# speculator_minor_mainboard_76mm_v1.net
KiCad netlist of a schematic drawn in EAGLE
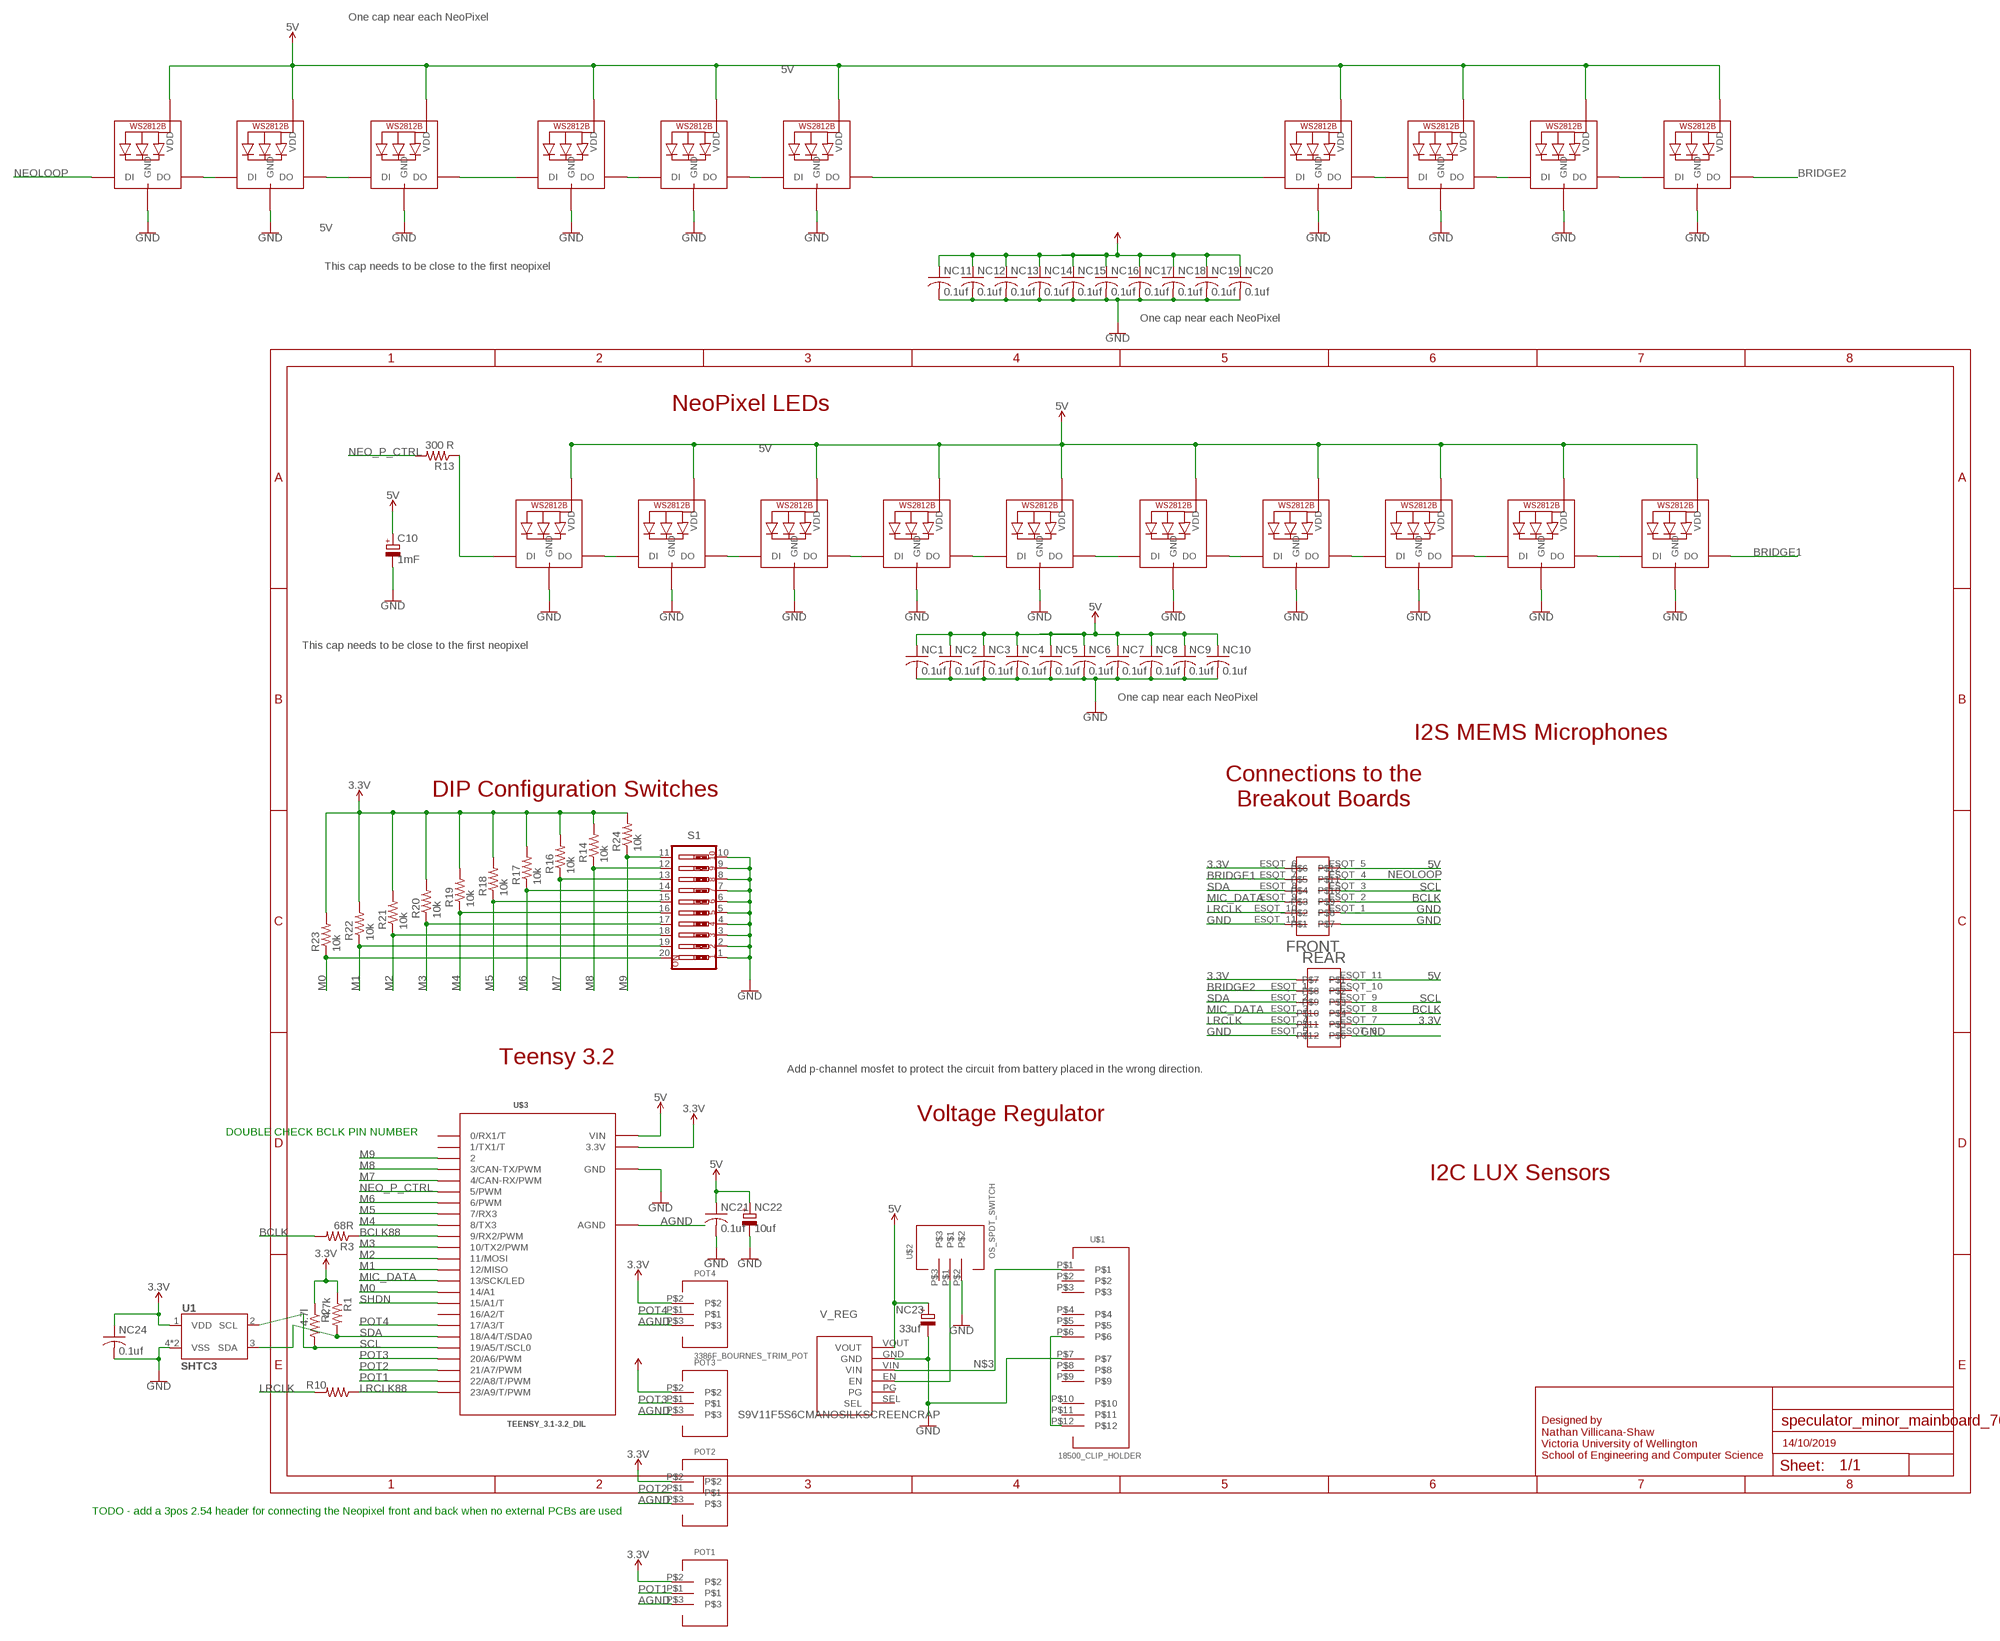
[diagram p0: schematic, sheet 1, part 1 of 2]
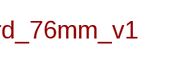
[diagram p1: schematic, sheet 1, part 2 of 2]

(export (version "E")
  (design (tool "Eeschema 10.0.6"))
  (components
    (comp (ref "C10")
      (value "1mF")
      (footprint "eagle-import:153CLV-1010")
      (libsource (lib "eagle-import") (part "CPOL-EU153CLV-1010"))
    )
    (comp (ref "FRONT")
      (value "SAMTEC_ESQT_2X6_THROUGH_HOLE")
      (footprint "eagle-import:SAMTEC_ESQT_2X6_THROUGH_HOLE")
      (libsource (lib "eagle-import") (part "SAMTEC_ESQT_2X6_THROUGH_HOLE"))
    )
    (comp (ref "NC1")
      (value "0.1uf")
      (footprint "eagle-import:C0805K")
      (libsource (lib "eagle-import") (part "C-USC0805K"))
    )
    (comp (ref "NC2")
      (value "0.1uf")
      (footprint "eagle-import:C0805K")
      (libsource (lib "eagle-import") (part "C-USC0805K"))
    )
    (comp (ref "NC3")
      (value "0.1uf")
      (footprint "eagle-import:C0805K")
      (libsource (lib "eagle-import") (part "C-USC0805K"))
    )
    (comp (ref "NC4")
      (value "0.1uf")
      (footprint "eagle-import:C0805K")
      (libsource (lib "eagle-import") (part "C-USC0805K"))
    )
    (comp (ref "NC5")
      (value "0.1uf")
      (footprint "eagle-import:C0805K")
      (libsource (lib "eagle-import") (part "C-USC0805K"))
    )
    (comp (ref "NC6")
      (value "0.1uf")
      (footprint "eagle-import:C0805K")
      (libsource (lib "eagle-import") (part "C-USC0805K"))
    )
    (comp (ref "NC7")
      (value "0.1uf")
      (footprint "eagle-import:C0805K")
      (libsource (lib "eagle-import") (part "C-USC0805K"))
    )
    (comp (ref "NC8")
      (value "0.1uf")
      (footprint "eagle-import:C0805K")
      (libsource (lib "eagle-import") (part "C-USC0805K"))
    )
    (comp (ref "NC9")
      (value "0.1uf")
      (footprint "eagle-import:C0805K")
      (libsource (lib "eagle-import") (part "C-USC0805K"))
    )
    (comp (ref "NC10")
      (value "0.1uf")
      (footprint "eagle-import:C0805K")
      (libsource (lib "eagle-import") (part "C-USC0805K"))
    )
    (comp (ref "NC11")
      (value "0.1uf")
      (footprint "eagle-import:C0805K")
      (libsource (lib "eagle-import") (part "C-USC0805K"))
    )
    (comp (ref "NC12")
      (value "0.1uf")
      (footprint "eagle-import:C0805K")
      (libsource (lib "eagle-import") (part "C-USC0805K"))
    )
    (comp (ref "NC13")
      (value "0.1uf")
      (footprint "eagle-import:C0805K")
      (libsource (lib "eagle-import") (part "C-USC0805K"))
    )
    (comp (ref "NC14")
      (value "0.1uf")
      (footprint "eagle-import:C0805K")
      (libsource (lib "eagle-import") (part "C-USC0805K"))
    )
    (comp (ref "NC15")
      (value "0.1uf")
      (footprint "eagle-import:C0805K")
      (libsource (lib "eagle-import") (part "C-USC0805K"))
    )
    (comp (ref "NC16")
      (value "0.1uf")
      (footprint "eagle-import:C0805K")
      (libsource (lib "eagle-import") (part "C-USC0805K"))
    )
    (comp (ref "NC17")
      (value "0.1uf")
      (footprint "eagle-import:C0805K")
      (libsource (lib "eagle-import") (part "C-USC0805K"))
    )
    (comp (ref "NC18")
      (value "0.1uf")
      (footprint "eagle-import:C0805K")
      (libsource (lib "eagle-import") (part "C-USC0805K"))
    )
    (comp (ref "NC19")
      (value "0.1uf")
      (footprint "eagle-import:C0805K")
      (libsource (lib "eagle-import") (part "C-USC0805K"))
    )
    (comp (ref "NC20")
      (value "0.1uf")
      (footprint "eagle-import:C0805K")
      (libsource (lib "eagle-import") (part "C-USC0805K"))
    )
    (comp (ref "NC21")
      (value "0.1uf")
      (footprint "eagle-import:C0805K")
      (libsource (lib "eagle-import") (part "C-USC0805K"))
    )
    (comp (ref "NC22")
      (value "10uf")
      (footprint "eagle-import:E2,5-7")
      (libsource (lib "eagle-import") (part "CPOL-EUE2.5-7"))
    )
    (comp (ref "NC23")
      (value "33uf")
      (footprint "eagle-import:E2,5-7")
      (libsource (lib "eagle-import") (part "CPOL-EUE2.5-7"))
    )
    (comp (ref "NC24")
      (value "0.1uf")
      (footprint "eagle-import:C0805K")
      (libsource (lib "eagle-import") (part "C-USC0805K"))
    )
    (comp (ref "NEO1")
      (value "WS2812B5050")
      (footprint "eagle-import:WS2812B")
      (libsource (lib "eagle-import") (part "WS2812B5050"))
    )
    (comp (ref "NEO2")
      (value "WS2812B5050")
      (footprint "eagle-import:WS2812B")
      (libsource (lib "eagle-import") (part "WS2812B5050"))
    )
    (comp (ref "NEO3")
      (value "WS2812B5050")
      (footprint "eagle-import:WS2812B")
      (libsource (lib "eagle-import") (part "WS2812B5050"))
    )
    (comp (ref "NEO4")
      (value "WS2812B5050")
      (footprint "eagle-import:WS2812B")
      (libsource (lib "eagle-import") (part "WS2812B5050"))
    )
    (comp (ref "NEO5")
      (value "WS2812B5050")
      (footprint "eagle-import:WS2812B")
      (libsource (lib "eagle-import") (part "WS2812B5050"))
    )
    (comp (ref "NEO6")
      (value "WS2812B5050")
      (footprint "eagle-import:WS2812B")
      (libsource (lib "eagle-import") (part "WS2812B5050"))
    )
    (comp (ref "NEO7")
      (value "WS2812B5050")
      (footprint "eagle-import:WS2812B")
      (libsource (lib "eagle-import") (part "WS2812B5050"))
    )
    (comp (ref "NEO8")
      (value "WS2812B5050")
      (footprint "eagle-import:WS2812B")
      (libsource (lib "eagle-import") (part "WS2812B5050"))
    )
    (comp (ref "NEO9")
      (value "WS2812B5050")
      (footprint "eagle-import:WS2812B")
      (libsource (lib "eagle-import") (part "WS2812B5050"))
    )
    (comp (ref "NEO10")
      (value "WS2812B5050")
      (footprint "eagle-import:WS2812B")
      (libsource (lib "eagle-import") (part "WS2812B5050"))
    )
    (comp (ref "NEO11")
      (value "WS2812B5050")
      (footprint "eagle-import:WS2812B")
      (libsource (lib "eagle-import") (part "WS2812B5050"))
    )
    (comp (ref "NEO12")
      (value "WS2812B5050")
      (footprint "eagle-import:WS2812B")
      (libsource (lib "eagle-import") (part "WS2812B5050"))
    )
    (comp (ref "NEO13")
      (value "WS2812B5050")
      (footprint "eagle-import:WS2812B")
      (libsource (lib "eagle-import") (part "WS2812B5050"))
    )
    (comp (ref "NEO14")
      (value "WS2812B5050")
      (footprint "eagle-import:WS2812B")
      (libsource (lib "eagle-import") (part "WS2812B5050"))
    )
    (comp (ref "NEO15")
      (value "WS2812B5050")
      (footprint "eagle-import:WS2812B")
      (libsource (lib "eagle-import") (part "WS2812B5050"))
    )
    (comp (ref "NEO16")
      (value "WS2812B5050")
      (footprint "eagle-import:WS2812B")
      (libsource (lib "eagle-import") (part "WS2812B5050"))
    )
    (comp (ref "NEO17")
      (value "WS2812B5050")
      (footprint "eagle-import:WS2812B")
      (libsource (lib "eagle-import") (part "WS2812B5050"))
    )
    (comp (ref "NEO18")
      (value "WS2812B5050")
      (footprint "eagle-import:WS2812B")
      (libsource (lib "eagle-import") (part "WS2812B5050"))
    )
    (comp (ref "NEO19")
      (value "WS2812B5050")
      (footprint "eagle-import:WS2812B")
      (libsource (lib "eagle-import") (part "WS2812B5050"))
    )
    (comp (ref "NEO20")
      (value "WS2812B5050")
      (footprint "eagle-import:WS2812B")
      (libsource (lib "eagle-import") (part "WS2812B5050"))
    )
    (comp (ref "POT1")
      (value "3386F_BOURNES_TRIM_POT")
      (footprint "eagle-import:3386_BOURNS_TRIM_POT")
      (libsource (lib "eagle-import") (part "3386F_BOURNES_TRIM_POT"))
    )
    (comp (ref "POT2")
      (value "3386F_BOURNES_TRIM_POT")
      (footprint "eagle-import:3386_BOURNS_TRIM_POT")
      (libsource (lib "eagle-import") (part "3386F_BOURNES_TRIM_POT"))
    )
    (comp (ref "POT3")
      (value "3386F_BOURNES_TRIM_POT")
      (footprint "eagle-import:3386_BOURNS_TRIM_POT")
      (libsource (lib "eagle-import") (part "3386F_BOURNES_TRIM_POT"))
    )
    (comp (ref "POT4")
      (value "3386F_BOURNES_TRIM_POT")
      (footprint "eagle-import:3386_BOURNS_TRIM_POT")
      (libsource (lib "eagle-import") (part "3386F_BOURNES_TRIM_POT"))
    )
    (comp (ref "R1")
      (value "4.7k")
      (footprint "eagle-import:R0805")
      (libsource (lib "eagle-import") (part "R-US_R0805"))
    )
    (comp (ref "R2")
      (value "4.7l")
      (footprint "eagle-import:R0805")
      (libsource (lib "eagle-import") (part "R-US_R0805"))
    )
    (comp (ref "R3")
      (value "68R")
      (footprint "eagle-import:R0805")
      (libsource (lib "eagle-import") (part "R-US_R0805"))
    )
    (comp (ref "R10")
      (value "68R")
      (footprint "eagle-import:R0805")
      (libsource (lib "eagle-import") (part "R-US_R0805"))
    )
    (comp (ref "R13")
      (value "300 R")
      (footprint "eagle-import:R0805")
      (libsource (lib "eagle-import") (part "R-US_R0805"))
    )
    (comp (ref "R14")
      (value "10k")
      (footprint "eagle-import:R0805")
      (libsource (lib "eagle-import") (part "R-US_R0805"))
    )
    (comp (ref "R16")
      (value "10k")
      (footprint "eagle-import:R0805")
      (libsource (lib "eagle-import") (part "R-US_R0805"))
    )
    (comp (ref "R17")
      (value "10k")
      (footprint "eagle-import:R0805")
      (libsource (lib "eagle-import") (part "R-US_R0805"))
    )
    (comp (ref "R18")
      (value "10k")
      (footprint "eagle-import:R0805")
      (libsource (lib "eagle-import") (part "R-US_R0805"))
    )
    (comp (ref "R19")
      (value "10k")
      (footprint "eagle-import:R0805")
      (libsource (lib "eagle-import") (part "R-US_R0805"))
    )
    (comp (ref "R20")
      (value "10k")
      (footprint "eagle-import:R0805")
      (libsource (lib "eagle-import") (part "R-US_R0805"))
    )
    (comp (ref "R21")
      (value "10k")
      (footprint "eagle-import:R0805")
      (libsource (lib "eagle-import") (part "R-US_R0805"))
    )
    (comp (ref "R22")
      (value "10k")
      (footprint "eagle-import:R0805")
      (libsource (lib "eagle-import") (part "R-US_R0805"))
    )
    (comp (ref "R23")
      (value "10k")
      (footprint "eagle-import:M0805")
      (libsource (lib "eagle-import") (part "R-US_M0805"))
    )
    (comp (ref "R24")
      (value "10k")
      (footprint "eagle-import:R0805")
      (libsource (lib "eagle-import") (part "R-US_R0805"))
    )
    (comp (ref "REAR")
      (value "SAMTEC_ESQT_2X6_THROUGH_HOLE")
      (footprint "eagle-import:SAMTEC_ESQT_2X6_THROUGH_HOLE")
      (libsource (lib "eagle-import") (part "SAMTEC_ESQT_2X6_THROUGH_HOLE"))
    )
    (comp (ref "S1")
      (value "SW_DIP-10")
      (footprint "eagle-import:EDG-10")
      (libsource (lib "eagle-import") (part "SW_DIP-10"))
    )
    (comp (ref "U$1")
      (value "18500_CLIP_HOLDER")
      (footprint "eagle-import:3PINBATTERY_CLIP")
      (fields (field (name "SPICEPREFIX") "X"))
      (libsource (lib "eagle-import") (part "18500_CLIP_HOLDER"))
    )
    (comp (ref "U$2")
      (value "OS_SPDT_SWITCH")
      (footprint "eagle-import:OS_SPDT_SLIDE_SWITCH")
      (libsource (lib "eagle-import") (part "OS_SPDT_SWITCH"))
    )
    (comp (ref "U$3")
      (value "TEENSY_3.1-3.2_DIL")
      (footprint "eagle-import:TEENSY_3.0-3.2&LC_DIL")
      (libsource (lib "eagle-import") (part "TEENSY_3.1-3.2_DIL"))
    )
    (comp (ref "U1")
      (value "SHTC3")
      (footprint "eagle-import:SHTC3")
      (libsource (lib "eagle-import") (part "SHTC3"))
    )
    (comp (ref "V_REG")
      (value "S9V11F5S6CMANOSILKSCREENCRAP")
      (footprint "eagle-import:S9V11F3S5CMA_BETTER_PINS")
      (libsource (lib "eagle-import") (part "S9V11F5S6CMANOSILKSCREENCRAP"))
    )
  )
  (nets
    (net (code "1") (name "/AGND") (class "Default")
      (node (ref "POT1") (pin "P$3") (pinfunction "P$3_P$3") (pintype "bidirectional"))
      (node (ref "POT2") (pin "P$3") (pinfunction "P$3_P$3") (pintype "bidirectional"))
      (node (ref "POT3") (pin "P$3") (pinfunction "P$3_P$3") (pintype "bidirectional"))
      (node (ref "POT4") (pin "P$3") (pinfunction "P$3_P$3") (pintype "bidirectional"))
      (node (ref "U$3") (pin "AGND") (pinfunction "AGND_AGND") (pintype "power_in"))
    )
    (net (code "2") (name "/BCLK") (class "Default")
      (node (ref "FRONT") (pin "ESQT_2") (pinfunction "P$3_ESQT_2") (pintype "bidirectional"))
      (node (ref "R3") (pin "2") (pinfunction "2_2") (pintype "passive"))
      (node (ref "REAR") (pin "ESQT_8") (pinfunction "P$10_ESQT_8") (pintype "bidirectional"))
    )
    (net (code "3") (name "/BCLK88") (class "Default")
      (node (ref "R3") (pin "1") (pinfunction "1_1") (pintype "passive"))
      (node (ref "U$3") (pin "9") (pinfunction "9/RX2/PWM_9") (pintype "bidirectional"))
    )
    (net (code "4") (name "/BRIDGE1") (class "Default")
      (node (ref "FRONT") (pin "ESQT_7") (pinfunction "P$11_ESQT_7") (pintype "bidirectional"))
      (node (ref "NEO10") (pin "2-DOUT") (pinfunction "DO_2-DOUT") (pintype "output"))
    )
    (net (code "5") (name "/BRIDGE2") (class "Default")
      (node (ref "NEO20") (pin "2-DOUT") (pinfunction "DO_2-DOUT") (pintype "output"))
      (node (ref "REAR") (pin "ESQT_1") (pinfunction "P$2_ESQT_1") (pintype "bidirectional"))
    )
    (net (code "6") (name "/LRCLK") (class "Default")
      (node (ref "FRONT") (pin "ESQT_10") (pinfunction "P$8_ESQT_10") (pintype "bidirectional"))
      (node (ref "R10") (pin "2") (pinfunction "2_2") (pintype "passive"))
      (node (ref "REAR") (pin "ESQT_4") (pinfunction "P$5_ESQT_4") (pintype "bidirectional"))
    )
    (net (code "7") (name "/LRCLK88") (class "Default")
      (node (ref "R10") (pin "1") (pinfunction "1_1") (pintype "passive"))
      (node (ref "U$3") (pin "23/A9") (pinfunction "23/A9/T/PWM_23/A9") (pintype "bidirectional"))
    )
    (net (code "8") (name "/M0") (class "Default")
      (node (ref "R23") (pin "1") (pinfunction "1_1") (pintype "passive"))
      (node (ref "S1") (pin "20") (pinfunction "20_20") (pintype "passive"))
      (node (ref "U$3") (pin "14/A0") (pinfunction "14/A1_14/A0") (pintype "bidirectional"))
    )
    (net (code "9") (name "/M1") (class "Default")
      (node (ref "R22") (pin "1") (pinfunction "1_1") (pintype "passive"))
      (node (ref "S1") (pin "19") (pinfunction "19_19") (pintype "passive"))
      (node (ref "U$3") (pin "12") (pinfunction "12/MISO_12") (pintype "bidirectional"))
    )
    (net (code "10") (name "/M2") (class "Default")
      (node (ref "R21") (pin "1") (pinfunction "1_1") (pintype "passive"))
      (node (ref "S1") (pin "18") (pinfunction "18_18") (pintype "passive"))
      (node (ref "U$3") (pin "11") (pinfunction "11/MOSI_11") (pintype "bidirectional"))
    )
    (net (code "11") (name "/M3") (class "Default")
      (node (ref "R20") (pin "1") (pinfunction "1_1") (pintype "passive"))
      (node (ref "S1") (pin "17") (pinfunction "17_17") (pintype "passive"))
      (node (ref "U$3") (pin "10") (pinfunction "10/TX2/PWM_10") (pintype "bidirectional"))
    )
    (net (code "12") (name "/M4") (class "Default")
      (node (ref "R19") (pin "1") (pinfunction "1_1") (pintype "passive"))
      (node (ref "S1") (pin "16") (pinfunction "16_16") (pintype "passive"))
      (node (ref "U$3") (pin "8") (pinfunction "8/TX3_8") (pintype "bidirectional"))
    )
    (net (code "13") (name "/M5") (class "Default")
      (node (ref "R18") (pin "1") (pinfunction "1_1") (pintype "passive"))
      (node (ref "S1") (pin "15") (pinfunction "15_15") (pintype "passive"))
      (node (ref "U$3") (pin "7") (pinfunction "7/RX3_7") (pintype "bidirectional"))
    )
    (net (code "14") (name "/M6") (class "Default")
      (node (ref "R17") (pin "1") (pinfunction "1_1") (pintype "passive"))
      (node (ref "S1") (pin "14") (pinfunction "14_14") (pintype "passive"))
      (node (ref "U$3") (pin "6") (pinfunction "6/PWM_6") (pintype "bidirectional"))
    )
    (net (code "15") (name "/M7") (class "Default")
      (node (ref "R16") (pin "1") (pinfunction "1_1") (pintype "passive"))
      (node (ref "S1") (pin "13") (pinfunction "13_13") (pintype "passive"))
      (node (ref "U$3") (pin "4") (pinfunction "4/CAN-RX/PWM_4") (pintype "bidirectional"))
    )
    (net (code "16") (name "/M8") (class "Default")
      (node (ref "R14") (pin "1") (pinfunction "1_1") (pintype "passive"))
      (node (ref "S1") (pin "12") (pinfunction "12_12") (pintype "passive"))
      (node (ref "U$3") (pin "3") (pinfunction "3/CAN-TX/PWM_3") (pintype "bidirectional"))
    )
    (net (code "17") (name "/M9") (class "Default")
      (node (ref "R24") (pin "1") (pinfunction "1_1") (pintype "passive"))
      (node (ref "S1") (pin "11") (pinfunction "11_11") (pintype "passive"))
      (node (ref "U$3") (pin "2") (pinfunction "2_2") (pintype "bidirectional"))
    )
    (net (code "18") (name "/MIC_DATA") (class "Default")
      (node (ref "FRONT") (pin "ESQT_9") (pinfunction "P$9_ESQT_9") (pintype "bidirectional"))
      (node (ref "REAR") (pin "ESQT_3") (pinfunction "P$4_ESQT_3") (pintype "bidirectional"))
      (node (ref "U$3") (pin "13") (pinfunction "13/SCK/LED_13") (pintype "bidirectional"))
    )
    (net (code "19") (name "/N$3") (class "Default")
      (node (ref "U$1") (pin "P$1") (pinfunction "P$1_P$1") (pintype "bidirectional"))
      (node (ref "V_REG") (pin "VIN") (pinfunction "VIN_VIN") (pintype "bidirectional"))
    )
    (net (code "20") (name "/NEOLOOP") (class "Default")
      (node (ref "FRONT") (pin "ESQT_4") (pinfunction "P$5_ESQT_4") (pintype "bidirectional"))
      (node (ref "NEO11") (pin "4-DIN") (pinfunction "DI_4-DIN") (pintype "input"))
    )
    (net (code "21") (name "/NEO_P_CTRL") (class "Default")
      (node (ref "R13") (pin "2") (pinfunction "2_2") (pintype "passive"))
      (node (ref "U$3") (pin "5") (pinfunction "5/PWM_5") (pintype "bidirectional"))
    )
    (net (code "22") (name "/POT1") (class "Default")
      (node (ref "POT1") (pin "P$1") (pinfunction "P$1_P$1") (pintype "bidirectional"))
      (node (ref "U$3") (pin "22/A8") (pinfunction "22/A8/T/PWM_22/A8") (pintype "bidirectional"))
    )
    (net (code "23") (name "/POT2") (class "Default")
      (node (ref "POT2") (pin "P$1") (pinfunction "P$1_P$1") (pintype "bidirectional"))
      (node (ref "U$3") (pin "21/A7") (pinfunction "21/A7/PWM_21/A7") (pintype "bidirectional"))
    )
    (net (code "24") (name "/POT3") (class "Default")
      (node (ref "POT3") (pin "P$1") (pinfunction "P$1_P$1") (pintype "bidirectional"))
      (node (ref "U$3") (pin "20/A6") (pinfunction "20/A6/PWM_20/A6") (pintype "bidirectional"))
    )
    (net (code "25") (name "/POT4") (class "Default")
      (node (ref "POT4") (pin "P$1") (pinfunction "P$1_P$1") (pintype "bidirectional"))
      (node (ref "U$3") (pin "17/A3") (pinfunction "17/A3/T_17/A3") (pintype "bidirectional"))
    )
    (net (code "26") (name "/SCL") (class "Default")
      (node (ref "FRONT") (pin "ESQT_3") (pinfunction "P$4_ESQT_3") (pintype "bidirectional"))
      (node (ref "R2") (pin "2") (pinfunction "2_2") (pintype "passive"))
      (node (ref "REAR") (pin "ESQT_9") (pinfunction "P$9_ESQT_9") (pintype "bidirectional"))
      (node (ref "U$3") (pin "19/A5") (pinfunction "19/A5/T/SCL0_19/A5") (pintype "bidirectional"))
      (node (ref "U1") (pin "2") (pinfunction "SCL_2") (pintype "bidirectional"))
    )
    (net (code "27") (name "/SDA") (class "Default")
      (node (ref "FRONT") (pin "ESQT_8") (pinfunction "P$10_ESQT_8") (pintype "bidirectional"))
      (node (ref "R1") (pin "2") (pinfunction "2_2") (pintype "passive"))
      (node (ref "REAR") (pin "ESQT_2") (pinfunction "P$3_ESQT_2") (pintype "bidirectional"))
      (node (ref "U$3") (pin "18/A4") (pinfunction "18/A4/T/SDA0_18/A4") (pintype "bidirectional"))
      (node (ref "U1") (pin "3") (pinfunction "SDA_3") (pintype "bidirectional"))
    )
    (net (code "28") (name "/SHDN") (class "Default")
      (node (ref "U$2") (pin "P$1") (pinfunction "P$1_P$1") (pintype "bidirectional"))
      (node (ref "U$3") (pin "15/A1") (pinfunction "15/A1/T_15/A1") (pintype "bidirectional"))
      (node (ref "V_REG") (pin "EN") (pinfunction "EN_EN") (pintype "bidirectional"))
    )
    (net (code "29") (name "3.3V") (class "Default")
      (node (ref "FRONT") (pin "ESQT_6") (pinfunction "P$12_ESQT_6") (pintype "bidirectional"))
      (node (ref "NC24") (pin "1") (pinfunction "1_1") (pintype "passive"))
      (node (ref "POT1") (pin "P$2") (pinfunction "P$2_P$2") (pintype "bidirectional"))
      (node (ref "POT2") (pin "P$2") (pinfunction "P$2_P$2") (pintype "bidirectional"))
      (node (ref "POT3") (pin "P$2") (pinfunction "P$2_P$2") (pintype "bidirectional"))
      (node (ref "POT4") (pin "P$2") (pinfunction "P$2_P$2") (pintype "bidirectional"))
      (node (ref "R1") (pin "1") (pinfunction "1_1") (pintype "passive"))
      (node (ref "R14") (pin "2") (pinfunction "2_2") (pintype "passive"))
      (node (ref "R16") (pin "2") (pinfunction "2_2") (pintype "passive"))
      (node (ref "R17") (pin "2") (pinfunction "2_2") (pintype "passive"))
      (node (ref "R18") (pin "2") (pinfunction "2_2") (pintype "passive"))
      (node (ref "R19") (pin "2") (pinfunction "2_2") (pintype "passive"))
      (node (ref "R2") (pin "1") (pinfunction "1_1") (pintype "passive"))
      (node (ref "R20") (pin "2") (pinfunction "2_2") (pintype "passive"))
      (node (ref "R21") (pin "2") (pinfunction "2_2") (pintype "passive"))
      (node (ref "R22") (pin "2") (pinfunction "2_2") (pintype "passive"))
      (node (ref "R23") (pin "2") (pinfunction "2_2") (pintype "passive"))
      (node (ref "R24") (pin "2") (pinfunction "2_2") (pintype "passive"))
      (node (ref "REAR") (pin "ESQT_0") (pinfunction "P$1_ESQT_0") (pintype "bidirectional"))
      (node (ref "REAR") (pin "ESQT_7") (pinfunction "P$11_ESQT_7") (pintype "bidirectional"))
      (node (ref "U$3") (pin "3.3V") (pinfunction "3.3V_3.3V") (pintype "power_in"))
      (node (ref "U1") (pin "1") (pinfunction "VDD_1") (pintype "bidirectional"))
    )
    (net (code "30") (name "5V") (class "Default")
      (node (ref "C10") (pin "+") (pinfunction "+_+") (pintype "passive"))
      (node (ref "FRONT") (pin "ESQT_5") (pinfunction "P$6_ESQT_5") (pintype "bidirectional"))
      (node (ref "NC1") (pin "1") (pinfunction "1_1") (pintype "passive"))
      (node (ref "NC10") (pin "1") (pinfunction "1_1") (pintype "passive"))
      (node (ref "NC11") (pin "1") (pinfunction "1_1") (pintype "passive"))
      (node (ref "NC12") (pin "1") (pinfunction "1_1") (pintype "passive"))
      (node (ref "NC13") (pin "1") (pinfunction "1_1") (pintype "passive"))
      (node (ref "NC14") (pin "1") (pinfunction "1_1") (pintype "passive"))
      (node (ref "NC15") (pin "1") (pinfunction "1_1") (pintype "passive"))
      (node (ref "NC16") (pin "1") (pinfunction "1_1") (pintype "passive"))
      (node (ref "NC17") (pin "1") (pinfunction "1_1") (pintype "passive"))
      (node (ref "NC18") (pin "1") (pinfunction "1_1") (pintype "passive"))
      (node (ref "NC19") (pin "1") (pinfunction "1_1") (pintype "passive"))
      (node (ref "NC2") (pin "1") (pinfunction "1_1") (pintype "passive"))
      (node (ref "NC20") (pin "1") (pinfunction "1_1") (pintype "passive"))
      (node (ref "NC21") (pin "1") (pinfunction "1_1") (pintype "passive"))
      (node (ref "NC22") (pin "+") (pinfunction "+_+") (pintype "passive"))
      (node (ref "NC23") (pin "+") (pinfunction "+_+") (pintype "passive"))
      (node (ref "NC3") (pin "1") (pinfunction "1_1") (pintype "passive"))
      (node (ref "NC4") (pin "1") (pinfunction "1_1") (pintype "passive"))
      (node (ref "NC5") (pin "1") (pinfunction "1_1") (pintype "passive"))
      (node (ref "NC6") (pin "1") (pinfunction "1_1") (pintype "passive"))
      (node (ref "NC7") (pin "1") (pinfunction "1_1") (pintype "passive"))
      (node (ref "NC8") (pin "1") (pinfunction "1_1") (pintype "passive"))
      (node (ref "NC9") (pin "1") (pinfunction "1_1") (pintype "passive"))
      (node (ref "NEO1") (pin "1-VDD") (pinfunction "VDD_1-VDD") (pintype "power_in"))
      (node (ref "NEO10") (pin "1-VDD") (pinfunction "VDD_1-VDD") (pintype "power_in"))
      (node (ref "NEO11") (pin "1-VDD") (pinfunction "VDD_1-VDD") (pintype "power_in"))
      (node (ref "NEO12") (pin "1-VDD") (pinfunction "VDD_1-VDD") (pintype "power_in"))
      (node (ref "NEO13") (pin "1-VDD") (pinfunction "VDD_1-VDD") (pintype "power_in"))
      (node (ref "NEO14") (pin "1-VDD") (pinfunction "VDD_1-VDD") (pintype "power_in"))
      (node (ref "NEO15") (pin "1-VDD") (pinfunction "VDD_1-VDD") (pintype "power_in"))
      (node (ref "NEO16") (pin "1-VDD") (pinfunction "VDD_1-VDD") (pintype "power_in"))
      (node (ref "NEO17") (pin "1-VDD") (pinfunction "VDD_1-VDD") (pintype "power_in"))
      (node (ref "NEO18") (pin "1-VDD") (pinfunction "VDD_1-VDD") (pintype "power_in"))
      (node (ref "NEO19") (pin "1-VDD") (pinfunction "VDD_1-VDD") (pintype "power_in"))
      (node (ref "NEO2") (pin "1-VDD") (pinfunction "VDD_1-VDD") (pintype "power_in"))
      (node (ref "NEO20") (pin "1-VDD") (pinfunction "VDD_1-VDD") (pintype "power_in"))
      (node (ref "NEO3") (pin "1-VDD") (pinfunction "VDD_1-VDD") (pintype "power_in"))
      (node (ref "NEO4") (pin "1-VDD") (pinfunction "VDD_1-VDD") (pintype "power_in"))
      (node (ref "NEO5") (pin "1-VDD") (pinfunction "VDD_1-VDD") (pintype "power_in"))
      (node (ref "NEO6") (pin "1-VDD") (pinfunction "VDD_1-VDD") (pintype "power_in"))
      (node (ref "NEO7") (pin "1-VDD") (pinfunction "VDD_1-VDD") (pintype "power_in"))
      (node (ref "NEO8") (pin "1-VDD") (pinfunction "VDD_1-VDD") (pintype "power_in"))
      (node (ref "NEO9") (pin "1-VDD") (pinfunction "VDD_1-VDD") (pintype "power_in"))
      (node (ref "REAR") (pin "ESQT_11") (pinfunction "P$7_ESQT_11") (pintype "bidirectional"))
      (node (ref "U$3") (pin "VIN") (pinfunction "VIN_VIN") (pintype "power_in"))
      (node (ref "V_REG") (pin "VOUT") (pinfunction "VOUT_VOUT") (pintype "bidirectional"))
    )
    (net (code "31") (name "GND") (class "Default")
      (node (ref "C10") (pin "-") (pinfunction "-_-") (pintype "passive"))
      (node (ref "FRONT") (pin "ESQT_0") (pinfunction "P$1_ESQT_0") (pintype "bidirectional"))
      (node (ref "FRONT") (pin "ESQT_1") (pinfunction "P$2_ESQT_1") (pintype "bidirectional"))
      (node (ref "FRONT") (pin "ESQT_11") (pinfunction "P$7_ESQT_11") (pintype "bidirectional"))
      (node (ref "NC1") (pin "2") (pinfunction "2_2") (pintype "passive"))
      (node (ref "NC10") (pin "2") (pinfunction "2_2") (pintype "passive"))
      (node (ref "NC11") (pin "2") (pinfunction "2_2") (pintype "passive"))
      (node (ref "NC12") (pin "2") (pinfunction "2_2") (pintype "passive"))
      (node (ref "NC13") (pin "2") (pinfunction "2_2") (pintype "passive"))
      (node (ref "NC14") (pin "2") (pinfunction "2_2") (pintype "passive"))
      (node (ref "NC15") (pin "2") (pinfunction "2_2") (pintype "passive"))
      (node (ref "NC16") (pin "2") (pinfunction "2_2") (pintype "passive"))
      (node (ref "NC17") (pin "2") (pinfunction "2_2") (pintype "passive"))
      (node (ref "NC18") (pin "2") (pinfunction "2_2") (pintype "passive"))
      (node (ref "NC19") (pin "2") (pinfunction "2_2") (pintype "passive"))
      (node (ref "NC2") (pin "2") (pinfunction "2_2") (pintype "passive"))
      (node (ref "NC20") (pin "2") (pinfunction "2_2") (pintype "passive"))
      (node (ref "NC21") (pin "2") (pinfunction "2_2") (pintype "passive"))
      (node (ref "NC22") (pin "-") (pinfunction "-_-") (pintype "passive"))
      (node (ref "NC23") (pin "-") (pinfunction "-_-") (pintype "passive"))
      (node (ref "NC24") (pin "2") (pinfunction "2_2") (pintype "passive"))
      (node (ref "NC3") (pin "2") (pinfunction "2_2") (pintype "passive"))
      (node (ref "NC4") (pin "2") (pinfunction "2_2") (pintype "passive"))
      (node (ref "NC5") (pin "2") (pinfunction "2_2") (pintype "passive"))
      (node (ref "NC6") (pin "2") (pinfunction "2_2") (pintype "passive"))
      (node (ref "NC7") (pin "2") (pinfunction "2_2") (pintype "passive"))
      (node (ref "NC8") (pin "2") (pinfunction "2_2") (pintype "passive"))
      (node (ref "NC9") (pin "2") (pinfunction "2_2") (pintype "passive"))
      (node (ref "NEO1") (pin "3-GND") (pinfunction "GND_3-GND") (pintype "power_in"))
      (node (ref "NEO10") (pin "3-GND") (pinfunction "GND_3-GND") (pintype "power_in"))
      (node (ref "NEO11") (pin "3-GND") (pinfunction "GND_3-GND") (pintype "power_in"))
      (node (ref "NEO12") (pin "3-GND") (pinfunction "GND_3-GND") (pintype "power_in"))
      (node (ref "NEO13") (pin "3-GND") (pinfunction "GND_3-GND") (pintype "power_in"))
      (node (ref "NEO14") (pin "3-GND") (pinfunction "GND_3-GND") (pintype "power_in"))
      (node (ref "NEO15") (pin "3-GND") (pinfunction "GND_3-GND") (pintype "power_in"))
      (node (ref "NEO16") (pin "3-GND") (pinfunction "GND_3-GND") (pintype "power_in"))
      (node (ref "NEO17") (pin "3-GND") (pinfunction "GND_3-GND") (pintype "power_in"))
      (node (ref "NEO18") (pin "3-GND") (pinfunction "GND_3-GND") (pintype "power_in"))
      (node (ref "NEO19") (pin "3-GND") (pinfunction "GND_3-GND") (pintype "power_in"))
      (node (ref "NEO2") (pin "3-GND") (pinfunction "GND_3-GND") (pintype "power_in"))
      (node (ref "NEO20") (pin "3-GND") (pinfunction "GND_3-GND") (pintype "power_in"))
      (node (ref "NEO3") (pin "3-GND") (pinfunction "GND_3-GND") (pintype "power_in"))
      (node (ref "NEO4") (pin "3-GND") (pinfunction "GND_3-GND") (pintype "power_in"))
      (node (ref "NEO5") (pin "3-GND") (pinfunction "GND_3-GND") (pintype "power_in"))
      (node (ref "NEO6") (pin "3-GND") (pinfunction "GND_3-GND") (pintype "power_in"))
      (node (ref "NEO7") (pin "3-GND") (pinfunction "GND_3-GND") (pintype "power_in"))
      (node (ref "NEO8") (pin "3-GND") (pinfunction "GND_3-GND") (pintype "power_in"))
      (node (ref "NEO9") (pin "3-GND") (pinfunction "GND_3-GND") (pintype "power_in"))
      (node (ref "REAR") (pin "ESQT_5") (pinfunction "P$6_ESQT_5") (pintype "bidirectional"))
      (node (ref "REAR") (pin "ESQT_6") (pinfunction "P$12_ESQT_6") (pintype "bidirectional"))
      (node (ref "S1") (pin "1") (pinfunction "1_1") (pintype "passive"))
      (node (ref "S1") (pin "10") (pinfunction "10_10") (pintype "passive"))
      (node (ref "S1") (pin "2") (pinfunction "2_2") (pintype "passive"))
      (node (ref "S1") (pin "3") (pinfunction "3_3") (pintype "passive"))
      (node (ref "S1") (pin "4") (pinfunction "4_4") (pintype "passive"))
      (node (ref "S1") (pin "5") (pinfunction "5_5") (pintype "passive"))
      (node (ref "S1") (pin "6") (pinfunction "6_6") (pintype "passive"))
      (node (ref "S1") (pin "7") (pinfunction "7_7") (pintype "passive"))
      (node (ref "S1") (pin "8") (pinfunction "8_8") (pintype "passive"))
      (node (ref "S1") (pin "9") (pinfunction "9_9") (pintype "passive"))
      (node (ref "U$1") (pin "P$7") (pinfunction "P$7_P$7") (pintype "bidirectional"))
      (node (ref "U$2") (pin "P$2") (pinfunction "P$2_P$2") (pintype "bidirectional"))
      (node (ref "U$3") (pin "GND") (pinfunction "GND_GND") (pintype "power_in"))
      (node (ref "U1") (pin "4") (pinfunction "VSS_4") (pintype "bidirectional"))
      (node (ref "U1") (pin "5") (pinfunction "VSS_5") (pintype "bidirectional"))
      (node (ref "V_REG") (pin "GND") (pinfunction "GND_GND") (pintype "bidirectional"))
    )
    (net (code "32") (name "Net-(NEO1-DI)") (class "Default")
      (node (ref "NEO1") (pin "4-DIN") (pinfunction "DI_4-DIN") (pintype "input"))
      (node (ref "R13") (pin "1") (pinfunction "1_1") (pintype "passive"))
    )
    (net (code "33") (name "Net-(NEO1-DO)") (class "Default")
      (node (ref "NEO1") (pin "2-DOUT") (pinfunction "DO_2-DOUT") (pintype "output"))
      (node (ref "NEO2") (pin "4-DIN") (pinfunction "DI_4-DIN") (pintype "input"))
    )
    (net (code "34") (name "Net-(NEO2-DO)") (class "Default")
      (node (ref "NEO2") (pin "2-DOUT") (pinfunction "DO_2-DOUT") (pintype "output"))
      (node (ref "NEO3") (pin "4-DIN") (pinfunction "DI_4-DIN") (pintype "input"))
    )
    (net (code "35") (name "Net-(NEO3-DO)") (class "Default")
      (node (ref "NEO3") (pin "2-DOUT") (pinfunction "DO_2-DOUT") (pintype "output"))
      (node (ref "NEO4") (pin "4-DIN") (pinfunction "DI_4-DIN") (pintype "input"))
    )
    (net (code "36") (name "Net-(NEO4-DO)") (class "Default")
      (node (ref "NEO4") (pin "2-DOUT") (pinfunction "DO_2-DOUT") (pintype "output"))
      (node (ref "NEO5") (pin "4-DIN") (pinfunction "DI_4-DIN") (pintype "input"))
    )
    (net (code "37") (name "Net-(NEO5-DO)") (class "Default")
      (node (ref "NEO5") (pin "2-DOUT") (pinfunction "DO_2-DOUT") (pintype "output"))
      (node (ref "NEO6") (pin "4-DIN") (pinfunction "DI_4-DIN") (pintype "input"))
    )
    (net (code "38") (name "Net-(NEO6-DO)") (class "Default")
      (node (ref "NEO6") (pin "2-DOUT") (pinfunction "DO_2-DOUT") (pintype "output"))
      (node (ref "NEO7") (pin "4-DIN") (pinfunction "DI_4-DIN") (pintype "input"))
    )
    (net (code "39") (name "Net-(NEO7-DO)") (class "Default")
      (node (ref "NEO7") (pin "2-DOUT") (pinfunction "DO_2-DOUT") (pintype "output"))
      (node (ref "NEO8") (pin "4-DIN") (pinfunction "DI_4-DIN") (pintype "input"))
    )
    (net (code "40") (name "Net-(NEO8-DO)") (class "Default")
      (node (ref "NEO8") (pin "2-DOUT") (pinfunction "DO_2-DOUT") (pintype "output"))
      (node (ref "NEO9") (pin "4-DIN") (pinfunction "DI_4-DIN") (pintype "input"))
    )
    (net (code "41") (name "Net-(NEO10-DI)") (class "Default")
      (node (ref "NEO10") (pin "4-DIN") (pinfunction "DI_4-DIN") (pintype "input"))
      (node (ref "NEO9") (pin "2-DOUT") (pinfunction "DO_2-DOUT") (pintype "output"))
    )
    (net (code "42") (name "Net-(NEO11-DO)") (class "Default")
      (node (ref "NEO11") (pin "2-DOUT") (pinfunction "DO_2-DOUT") (pintype "output"))
      (node (ref "NEO12") (pin "4-DIN") (pinfunction "DI_4-DIN") (pintype "input"))
    )
    (net (code "43") (name "Net-(NEO12-DO)") (class "Default")
      (node (ref "NEO12") (pin "2-DOUT") (pinfunction "DO_2-DOUT") (pintype "output"))
      (node (ref "NEO13") (pin "4-DIN") (pinfunction "DI_4-DIN") (pintype "input"))
    )
    (net (code "44") (name "Net-(NEO13-DO)") (class "Default")
      (node (ref "NEO13") (pin "2-DOUT") (pinfunction "DO_2-DOUT") (pintype "output"))
      (node (ref "NEO14") (pin "4-DIN") (pinfunction "DI_4-DIN") (pintype "input"))
    )
    (net (code "45") (name "Net-(NEO14-DO)") (class "Default")
      (node (ref "NEO14") (pin "2-DOUT") (pinfunction "DO_2-DOUT") (pintype "output"))
      (node (ref "NEO15") (pin "4-DIN") (pinfunction "DI_4-DIN") (pintype "input"))
    )
    (net (code "46") (name "Net-(NEO15-DO)") (class "Default")
      (node (ref "NEO15") (pin "2-DOUT") (pinfunction "DO_2-DOUT") (pintype "output"))
      (node (ref "NEO16") (pin "4-DIN") (pinfunction "DI_4-DIN") (pintype "input"))
    )
    (net (code "47") (name "Net-(NEO16-DO)") (class "Default")
      (node (ref "NEO16") (pin "2-DOUT") (pinfunction "DO_2-DOUT") (pintype "output"))
      (node (ref "NEO17") (pin "4-DIN") (pinfunction "DI_4-DIN") (pintype "input"))
    )
    (net (code "48") (name "Net-(NEO17-DO)") (class "Default")
      (node (ref "NEO17") (pin "2-DOUT") (pinfunction "DO_2-DOUT") (pintype "output"))
      (node (ref "NEO18") (pin "4-DIN") (pinfunction "DI_4-DIN") (pintype "input"))
    )
    (net (code "49") (name "Net-(NEO18-DO)") (class "Default")
      (node (ref "NEO18") (pin "2-DOUT") (pinfunction "DO_2-DOUT") (pintype "output"))
      (node (ref "NEO19") (pin "4-DIN") (pinfunction "DI_4-DIN") (pintype "input"))
    )
    (net (code "50") (name "Net-(NEO19-DO)") (class "Default")
      (node (ref "NEO19") (pin "2-DOUT") (pinfunction "DO_2-DOUT") (pintype "output"))
      (node (ref "NEO20") (pin "4-DIN") (pinfunction "DI_4-DIN") (pintype "input"))
    )
    (net (code "51") (name "Net-(U$1-PadP$12)") (class "Default")
      (node (ref "U$1") (pin "P$12") (pinfunction "P$12_P$12") (pintype "bidirectional"))
      (node (ref "U$1") (pin "P$6") (pinfunction "P$6_P$6") (pintype "bidirectional"))
    )
    (net (code "52") (name "unconnected-(REAR-P$8-PadESQT_10)") (class "Default")
      (node (ref "REAR") (pin "ESQT_10") (pinfunction "P$8_ESQT_10") (pintype "bidirectional"))
    )
    (net (code "53") (name "unconnected-(U$1-PadP$2)") (class "Default")
      (node (ref "U$1") (pin "P$2") (pinfunction "P$2_P$2") (pintype "bidirectional"))
    )
    (net (code "54") (name "unconnected-(U$1-PadP$3)") (class "Default")
      (node (ref "U$1") (pin "P$3") (pinfunction "P$3_P$3") (pintype "bidirectional"))
    )
    (net (code "55") (name "unconnected-(U$1-PadP$4)") (class "Default")
      (node (ref "U$1") (pin "P$4") (pinfunction "P$4_P$4") (pintype "bidirectional"))
    )
    (net (code "56") (name "unconnected-(U$1-PadP$5)") (class "Default")
      (node (ref "U$1") (pin "P$5") (pinfunction "P$5_P$5") (pintype "bidirectional"))
    )
    (net (code "57") (name "unconnected-(U$1-PadP$8)") (class "Default")
      (node (ref "U$1") (pin "P$8") (pinfunction "P$8_P$8") (pintype "bidirectional"))
    )
    (net (code "58") (name "unconnected-(U$1-PadP$9)") (class "Default")
      (node (ref "U$1") (pin "P$9") (pinfunction "P$9_P$9") (pintype "bidirectional"))
    )
    (net (code "59") (name "unconnected-(U$1-PadP$10)") (class "Default")
      (node (ref "U$1") (pin "P$10") (pinfunction "P$10_P$10") (pintype "bidirectional"))
    )
    (net (code "60") (name "unconnected-(U$1-PadP$11)") (class "Default")
      (node (ref "U$1") (pin "P$11") (pinfunction "P$11_P$11") (pintype "bidirectional"))
    )
    (net (code "61") (name "unconnected-(U$2-PadP$3)") (class "Default")
      (node (ref "U$2") (pin "P$3") (pinfunction "P$3_P$3") (pintype "bidirectional"))
    )
    (net (code "62") (name "unconnected-(U$3-0{slash}RX1{slash}T-Pad0)") (class "Default")
      (node (ref "U$3") (pin "0") (pinfunction "0/RX1/T_0") (pintype "bidirectional"))
    )
    (net (code "63") (name "unconnected-(U$3-1{slash}TX1{slash}T-Pad1)") (class "Default")
      (node (ref "U$3") (pin "1") (pinfunction "1/TX1/T_1") (pintype "bidirectional"))
    )
    (net (code "64") (name "unconnected-(U$3-16{slash}A2{slash}T-Pad16{slash}A2)") (class "Default")
      (node (ref "U$3") (pin "16/A2") (pinfunction "16/A2/T_16/A2") (pintype "bidirectional"))
    )
    (net (code "65") (name "unconnected-(V_REG-PadPG)") (class "Default")
      (node (ref "V_REG") (pin "PG") (pinfunction "PG_PG") (pintype "bidirectional"))
    )
    (net (code "66") (name "unconnected-(V_REG-PadSEL)") (class "Default")
      (node (ref "V_REG") (pin "SEL") (pinfunction "SEL_SEL") (pintype "bidirectional"))
    )
  )
)
